# Power_USB.net
KiCad netlist of a schematic drawn in Altium Designer
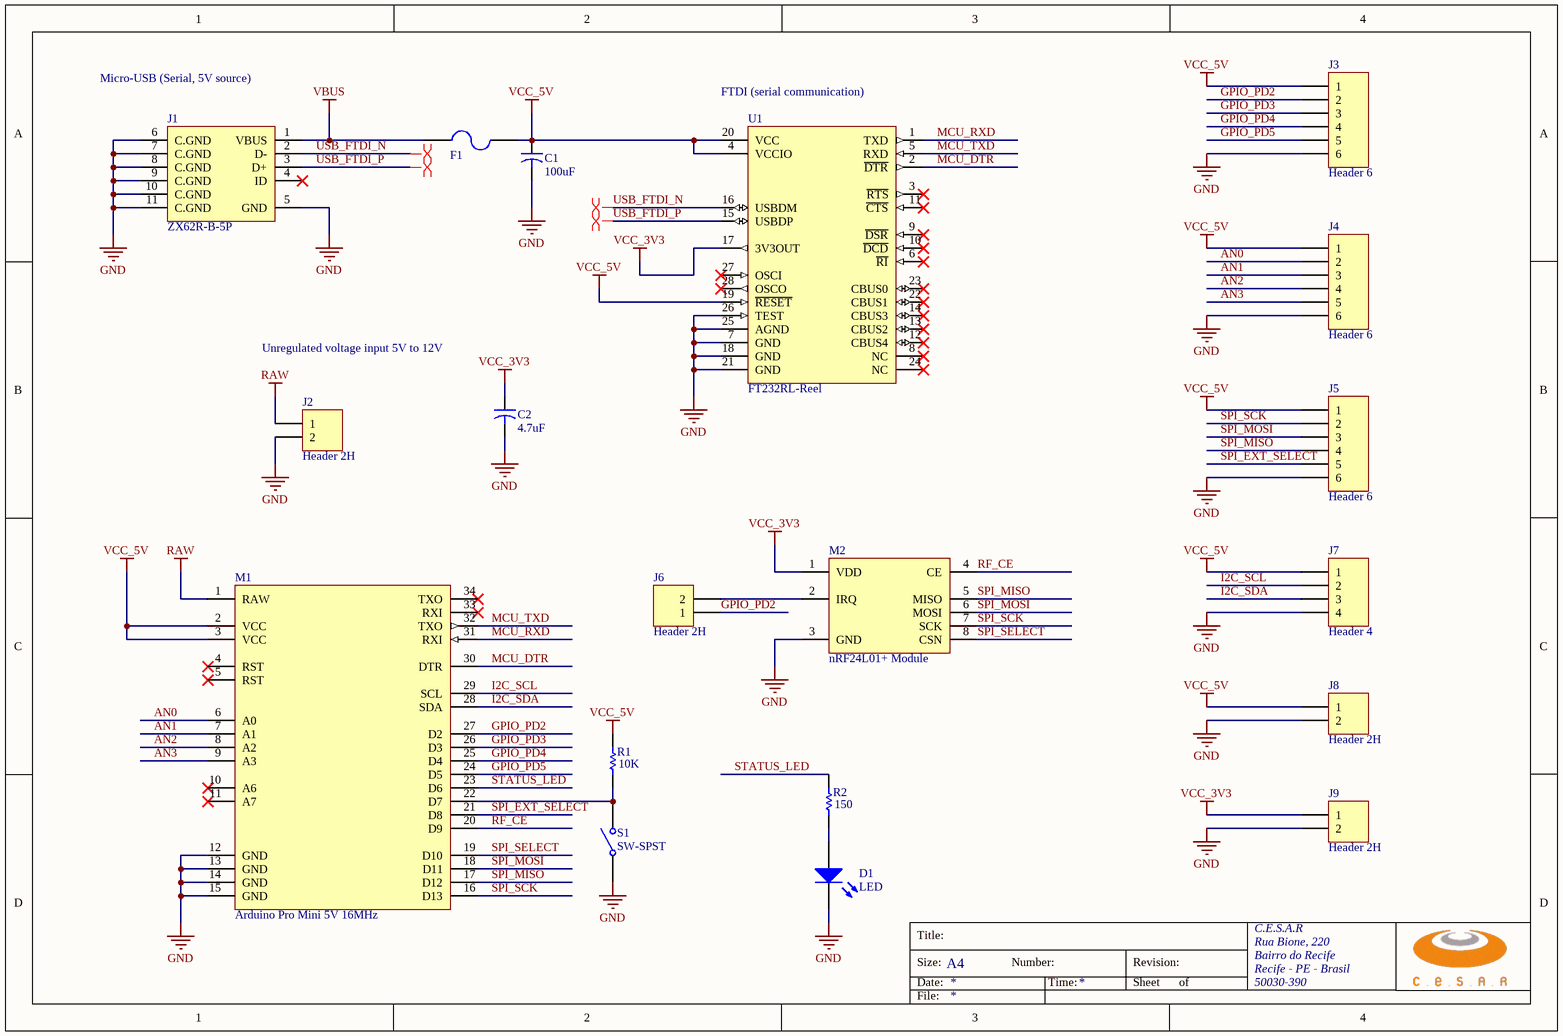
[diagram p0: Power_USB.SchDoc]

(export (version "E")
  (design (tool "Eeschema 10.0.6"))
  (components
    (comp (ref "C1")
      (value "100uF")
      (footprint "CAP Radial 100uF")
      (description "4.7µF 10V Ceramic Capacitor X5R 0603")
      (fields (field (name "Comment") "CAPC1608L") (field (name "PUBLISHER") "Altium Limited"))
      (libsource (lib "KNoT_Thing") (part "CAPC1608L"))
    )
    (comp (ref "C2")
      (value "4.7uF")
      (footprint "CAP RADIAL MINIATURE")
      (description "4.7µF 10V Ceramic Capacitor X5R 0603")
      (fields (field (name "Comment") "CAPC1608L") (field (name "PUBLISHER") "Altium Limited"))
      (libsource (lib "KNoT_Thing") (part "CAPC1608L"))
    )
    (comp (ref "D1")
      (value "LED")
      (footprint "LED")
      (description "Typical RED, GREEN, YELLOW, AMBER GaAs LED")
      (fields (field (name "PUBLISHER") "Altium Limited"))
      (libsource (lib "KNoT_Thing") (part "LED"))
    )
    (comp (ref "F1")
      (value "0402L050SLKR")
      (footprint "0805L")
      (description "PTC Resettable Fuse 6V 500mA Ih Surface Mount 0402 (1005 Metric), Concave")
      (libsource (lib "KNoT_Thing") (part "Fuse 2"))
    )
    (comp (ref "J1")
      (value "ZX62R-B-5P")
      (footprint "Micro USB b")
      (description "USB Connector")
      (libsource (lib "KNoT_Thing") (part "ZX62R-B-5P"))
    )
    (comp (ref "J2")
      (value "Header 2H")
      (footprint "HDR1X2")
      (description "Header, 2-Pin, Right Angle")
      (fields (field (name "PUBLISHER") "Altium Limited"))
      (libsource (lib "KNoT_Thing") (part "Header 2H"))
    )
    (comp (ref "J3")
      (value "Header 6")
      (footprint "HDR1X6")
      (description "Header, 6-Pin")
      (fields (field (name "PUBLISHER") "Altium Limited"))
      (libsource (lib "KNoT_Thing") (part "Header 6"))
    )
    (comp (ref "J4")
      (value "Header 6")
      (footprint "HDR1X6")
      (description "Header, 6-Pin")
      (fields (field (name "PUBLISHER") "Altium Limited"))
      (libsource (lib "KNoT_Thing") (part "Header 6"))
    )
    (comp (ref "J5")
      (value "Header 6")
      (footprint "HDR1X6")
      (description "Header, 6-Pin")
      (fields (field (name "PUBLISHER") "Altium Limited"))
      (libsource (lib "KNoT_Thing") (part "Header 6"))
    )
    (comp (ref "J6")
      (value "Header 2H")
      (footprint "HDR1X2")
      (description "Header, 2-Pin, Right Angle")
      (fields (field (name "PUBLISHER") "Altium Limited"))
      (libsource (lib "") (part "Header 2H_1"))
    )
    (comp (ref "J7")
      (value "Header 4")
      (footprint "HDR1X4")
      (description "Header, 4-Pin")
      (fields (field (name "PUBLISHER") "Altium Limited"))
      (libsource (lib "KNoT_Thing") (part "Header 4"))
    )
    (comp (ref "J8")
      (value "Header 2H")
      (footprint "HDR1X2")
      (description "Header, 2-Pin, Right Angle")
      (fields (field (name "PUBLISHER") "Altium Limited"))
      (libsource (lib "KNoT_Thing") (part "Header 2H"))
    )
    (comp (ref "J9")
      (value "Header 2H")
      (footprint "HDR1X2")
      (description "Header, 2-Pin, Right Angle")
      (fields (field (name "PUBLISHER") "Altium Limited"))
      (libsource (lib "KNoT_Thing") (part "Header 2H"))
    )
    (comp (ref "M1")
      (value "Arduino Pro Mini 5V 16MHz")
      (footprint "Arduino Pro Mini")
      (libsource (lib "KNoT_Thing") (part "Arduino Pro Mini 5V 16MHz"))
    )
    (comp (ref "M2")
      (value "nRF24L01+ Module")
      (footprint "nRF24L01+ Module")
      (libsource (lib "KNoT_Thing") (part "nRF24L01+ Module"))
    )
    (comp (ref "R1")
      (value "10K")
      (footprint "AXIAL-3mm")
      (description "Resistor")
      (fields (field (name "Comment") "Res1") (field (name "PUBLISHER") "Altium Limited"))
      (libsource (lib "KNoT_Thing") (part "Res1"))
    )
    (comp (ref "R2")
      (value "150")
      (footprint "AXIAL-3mm")
      (description "Resistor")
      (fields (field (name "Comment") "Res1") (field (name "PUBLISHER") "Altium Limited"))
      (libsource (lib "KNoT_Thing") (part "Res1"))
    )
    (comp (ref "S1")
      (value "SW-SPST")
      (footprint "SWITCH TS-1181")
      (description "Single-Pole, Single-Throw Switch")
      (fields (field (name "PUBLISHER") "Altium Limited"))
      (libsource (lib "KNoT_Thing") (part "SW-SPST"))
    )
    (comp (ref "U1")
      (value "FT232RL-Reel")
      (footprint "SSOP-28_N")
      (description "USB UART Asynchronous Serial Data Transfer Chip, 28-pin SSOP, Tape and Reel")
      (fields (field (name "MANUFACTURER") "FTDI"))
      (libsource (lib "KNoT_Thing") (part "FT232RL-Reel"))
    )
  )
  (nets
    (net (code "1") (name "/AN0") (class "Default")
      (node (ref "J4") (pin "2") (pinfunction "2_2") (pintype "passive"))
      (node (ref "M1") (pin "6") (pinfunction "A0_6") (pintype "passive"))
    )
    (net (code "2") (name "/AN1") (class "Default")
      (node (ref "J4") (pin "3") (pinfunction "3_3") (pintype "passive"))
      (node (ref "M1") (pin "7") (pinfunction "A1_7") (pintype "passive"))
    )
    (net (code "3") (name "/AN2") (class "Default")
      (node (ref "J4") (pin "4") (pinfunction "4_4") (pintype "passive"))
      (node (ref "M1") (pin "8") (pinfunction "A2_8") (pintype "passive"))
    )
    (net (code "4") (name "/AN3") (class "Default")
      (node (ref "J4") (pin "5") (pinfunction "5_5") (pintype "passive"))
      (node (ref "M1") (pin "9") (pinfunction "A3_9") (pintype "passive"))
    )
    (net (code "5") (name "/GPIO_PD2") (class "Default")
      (node (ref "J3") (pin "2") (pinfunction "2_2") (pintype "passive"))
      (node (ref "J6") (pin "1") (pinfunction "1_1") (pintype "passive"))
      (node (ref "M1") (pin "27") (pinfunction "D2_27") (pintype "passive"))
    )
    (net (code "6") (name "/GPIO_PD3") (class "Default")
      (node (ref "J3") (pin "3") (pinfunction "3_3") (pintype "passive"))
      (node (ref "M1") (pin "26") (pinfunction "D3_26") (pintype "passive"))
    )
    (net (code "7") (name "/GPIO_PD4") (class "Default")
      (node (ref "J3") (pin "4") (pinfunction "4_4") (pintype "passive"))
      (node (ref "M1") (pin "25") (pinfunction "D4_25") (pintype "passive"))
    )
    (net (code "8") (name "/GPIO_PD5") (class "Default")
      (node (ref "J3") (pin "5") (pinfunction "5_5") (pintype "passive"))
      (node (ref "M1") (pin "24") (pinfunction "D5_24") (pintype "passive"))
    )
    (net (code "9") (name "/I2C_SCL") (class "Default")
      (node (ref "J7") (pin "2") (pinfunction "2_2") (pintype "passive"))
      (node (ref "M1") (pin "29") (pinfunction "SCL_29") (pintype "passive"))
    )
    (net (code "10") (name "/I2C_SDA") (class "Default")
      (node (ref "J7") (pin "3") (pinfunction "3_3") (pintype "passive"))
      (node (ref "M1") (pin "28") (pinfunction "SDA_28") (pintype "passive"))
    )
    (net (code "11") (name "/MCU_DTR") (class "Default")
      (node (ref "M1") (pin "30") (pinfunction "DTR_30") (pintype "passive"))
      (node (ref "U1") (pin "2") (pinfunction "~{DTR}_2") (pintype "output"))
    )
    (net (code "12") (name "/MCU_RXD") (class "Default")
      (node (ref "M1") (pin "31") (pinfunction "RXI_31") (pintype "input"))
      (node (ref "U1") (pin "1") (pinfunction "TXD_1") (pintype "output"))
    )
    (net (code "13") (name "/MCU_TXD") (class "Default")
      (node (ref "M1") (pin "32") (pinfunction "TXO_32") (pintype "output"))
      (node (ref "U1") (pin "5") (pinfunction "RXD_5") (pintype "input"))
    )
    (net (code "14") (name "/RF_CE") (class "Default")
      (node (ref "M1") (pin "20") (pinfunction "D9_20") (pintype "passive"))
      (node (ref "M2") (pin "4") (pinfunction "CE_4") (pintype "passive"))
    )
    (net (code "15") (name "/SPI_EXT_SELECT") (class "Default")
      (node (ref "J5") (pin "5") (pinfunction "5_5") (pintype "passive"))
      (node (ref "M1") (pin "21") (pinfunction "D8_21") (pintype "passive"))
    )
    (net (code "16") (name "/SPI_MISO") (class "Default")
      (node (ref "J5") (pin "4") (pinfunction "4_4") (pintype "passive"))
      (node (ref "M1") (pin "17") (pinfunction "D12_17") (pintype "passive"))
      (node (ref "M2") (pin "5") (pinfunction "MISO_5") (pintype "passive"))
    )
    (net (code "17") (name "/SPI_MOSI") (class "Default")
      (node (ref "J5") (pin "3") (pinfunction "3_3") (pintype "passive"))
      (node (ref "M1") (pin "18") (pinfunction "D11_18") (pintype "passive"))
      (node (ref "M2") (pin "6") (pinfunction "MOSI_6") (pintype "passive"))
    )
    (net (code "18") (name "/SPI_SCK") (class "Default")
      (node (ref "J5") (pin "2") (pinfunction "2_2") (pintype "passive"))
      (node (ref "M1") (pin "16") (pinfunction "D13_16") (pintype "passive"))
      (node (ref "M2") (pin "7") (pinfunction "SCK_7") (pintype "passive"))
    )
    (net (code "19") (name "/SPI_SELECT") (class "Default")
      (node (ref "M1") (pin "19") (pinfunction "D10_19") (pintype "passive"))
      (node (ref "M2") (pin "8") (pinfunction "CSN_8") (pintype "passive"))
    )
    (net (code "20") (name "/STATUS_LED") (class "Default")
      (node (ref "M1") (pin "23") (pinfunction "D6_23") (pintype "passive"))
      (node (ref "R2") (pin "1") (pinfunction "1_1") (pintype "passive"))
    )
    (net (code "21") (name "/USB_FTDI_N") (class "Default")
      (node (ref "J1") (pin "2") (pinfunction "D-_2") (pintype "passive"))
      (node (ref "U1") (pin "16") (pinfunction "USBDM_16") (pintype "bidirectional"))
    )
    (net (code "22") (name "/USB_FTDI_P") (class "Default")
      (node (ref "J1") (pin "3") (pinfunction "D+_3") (pintype "passive"))
      (node (ref "U1") (pin "15") (pinfunction "USBDP_15") (pintype "bidirectional"))
    )
    (net (code "23") (name "GND") (class "Default")
      (node (ref "C1") (pin "2") (pinfunction "2_2") (pintype "passive"))
      (node (ref "C2") (pin "2") (pinfunction "2_2") (pintype "passive"))
      (node (ref "D1") (pin "2") (pinfunction "K_2") (pintype "passive"))
      (node (ref "J1") (pin "10") (pinfunction "C.GND_10") (pintype "passive"))
      (node (ref "J1") (pin "11") (pinfunction "C.GND_11") (pintype "passive"))
      (node (ref "J1") (pin "5") (pinfunction "GND_5") (pintype "passive"))
      (node (ref "J1") (pin "6") (pinfunction "C.GND_6") (pintype "passive"))
      (node (ref "J1") (pin "7") (pinfunction "C.GND_7") (pintype "passive"))
      (node (ref "J1") (pin "8") (pinfunction "C.GND_8") (pintype "passive"))
      (node (ref "J1") (pin "9") (pinfunction "C.GND_9") (pintype "passive"))
      (node (ref "J2") (pin "2") (pinfunction "2_2") (pintype "passive"))
      (node (ref "J3") (pin "6") (pinfunction "6_6") (pintype "passive"))
      (node (ref "J4") (pin "6") (pinfunction "6_6") (pintype "passive"))
      (node (ref "J5") (pin "6") (pinfunction "6_6") (pintype "passive"))
      (node (ref "J7") (pin "4") (pinfunction "4_4") (pintype "passive"))
      (node (ref "J8") (pin "2") (pinfunction "2_2") (pintype "passive"))
      (node (ref "J9") (pin "2") (pinfunction "2_2") (pintype "passive"))
      (node (ref "M1") (pin "12") (pinfunction "GND_12") (pintype "passive"))
      (node (ref "M1") (pin "13") (pinfunction "GND_13") (pintype "passive"))
      (node (ref "M1") (pin "14") (pinfunction "GND_14") (pintype "passive"))
      (node (ref "M1") (pin "15") (pinfunction "GND_15") (pintype "passive"))
      (node (ref "M2") (pin "3") (pinfunction "GND_3") (pintype "passive"))
      (node (ref "S1") (pin "1") (pinfunction "COMMON_1") (pintype "passive"))
      (node (ref "U1") (pin "18") (pinfunction "GND_18") (pintype "power_in"))
      (node (ref "U1") (pin "21") (pinfunction "GND_21") (pintype "power_in"))
      (node (ref "U1") (pin "25") (pinfunction "AGND_25") (pintype "power_in"))
      (node (ref "U1") (pin "26") (pinfunction "TEST_26") (pintype "input"))
      (node (ref "U1") (pin "7") (pinfunction "GND_7") (pintype "power_in"))
    )
    (net (code "24") (name "Net-(D1-A)") (class "Default")
      (node (ref "D1") (pin "1") (pinfunction "A_1") (pintype "passive"))
      (node (ref "R2") (pin "2") (pinfunction "2_2") (pintype "passive"))
    )
    (net (code "25") (name "Net-(M1-D7)") (class "Default")
      (node (ref "M1") (pin "22") (pinfunction "D7_22") (pintype "passive"))
      (node (ref "R1") (pin "2") (pinfunction "2_2") (pintype "passive"))
      (node (ref "S1") (pin "2") (pinfunction "NO_2") (pintype "passive"))
    )
    (net (code "26") (name "Net-(M2-IRQ)") (class "Default")
      (node (ref "J6") (pin "2") (pinfunction "2_2") (pintype "passive"))
      (node (ref "M2") (pin "2") (pinfunction "IRQ_2") (pintype "passive"))
    )
    (net (code "27") (name "RAW") (class "Default")
      (node (ref "J2") (pin "1") (pinfunction "1_1") (pintype "passive"))
      (node (ref "M1") (pin "1") (pinfunction "RAW_1") (pintype "passive"))
    )
    (net (code "28") (name "VBUS") (class "Default")
      (node (ref "F1") (pin "1") (pinfunction "1_1") (pintype "passive"))
      (node (ref "J1") (pin "1") (pinfunction "VBUS_1") (pintype "passive"))
    )
    (net (code "29") (name "VCC_3V3") (class "Default")
      (node (ref "C2") (pin "1") (pinfunction "1_1") (pintype "passive"))
      (node (ref "J9") (pin "1") (pinfunction "1_1") (pintype "passive"))
      (node (ref "M2") (pin "1") (pinfunction "VDD_1") (pintype "passive"))
      (node (ref "U1") (pin "17") (pinfunction "3V3OUT_17") (pintype "output"))
    )
    (net (code "30") (name "VCC_5V") (class "Default")
      (node (ref "C1") (pin "1") (pinfunction "1_1") (pintype "passive"))
      (node (ref "F1") (pin "2") (pinfunction "2_2") (pintype "passive"))
      (node (ref "J3") (pin "1") (pinfunction "1_1") (pintype "passive"))
      (node (ref "J4") (pin "1") (pinfunction "1_1") (pintype "passive"))
      (node (ref "J5") (pin "1") (pinfunction "1_1") (pintype "passive"))
      (node (ref "J7") (pin "1") (pinfunction "1_1") (pintype "passive"))
      (node (ref "J8") (pin "1") (pinfunction "1_1") (pintype "passive"))
      (node (ref "M1") (pin "2") (pinfunction "VCC_2") (pintype "passive"))
      (node (ref "M1") (pin "3") (pinfunction "VCC_3") (pintype "passive"))
      (node (ref "R1") (pin "1") (pinfunction "1_1") (pintype "passive"))
      (node (ref "U1") (pin "19") (pinfunction "~{RESET}_19") (pintype "input"))
      (node (ref "U1") (pin "20") (pinfunction "VCC_20") (pintype "power_in"))
      (node (ref "U1") (pin "4") (pinfunction "VCCIO_4") (pintype "power_in"))
    )
    (net (code "31") (name "unconnected-(J1-ID-Pad4)") (class "Default")
      (node (ref "J1") (pin "4") (pinfunction "ID_4") (pintype "passive+no_connect"))
    )
    (net (code "32") (name "unconnected-(M1-A6-Pad10)") (class "Default")
      (node (ref "M1") (pin "10") (pinfunction "A6_10") (pintype "passive+no_connect"))
    )
    (net (code "33") (name "unconnected-(M1-A7-Pad11)") (class "Default")
      (node (ref "M1") (pin "11") (pinfunction "A7_11") (pintype "passive+no_connect"))
    )
    (net (code "34") (name "unconnected-(M1-RST-Pad4)") (class "Default")
      (node (ref "M1") (pin "4") (pinfunction "RST_4") (pintype "passive+no_connect"))
    )
    (net (code "35") (name "unconnected-(M1-RST-Pad5)") (class "Default")
      (node (ref "M1") (pin "5") (pinfunction "RST_5") (pintype "passive+no_connect"))
    )
    (net (code "36") (name "unconnected-(M1-RXI-Pad33)") (class "Default")
      (node (ref "M1") (pin "33") (pinfunction "RXI_33") (pintype "passive+no_connect"))
    )
    (net (code "37") (name "unconnected-(M1-TXO-Pad34)") (class "Default")
      (node (ref "M1") (pin "34") (pinfunction "TXO_34") (pintype "passive+no_connect"))
    )
    (net (code "38") (name "unconnected-(U1-CBUS0-Pad23)") (class "Default")
      (node (ref "U1") (pin "23") (pinfunction "CBUS0_23") (pintype "bidirectional+no_connect"))
    )
    (net (code "39") (name "unconnected-(U1-CBUS1-Pad22)") (class "Default")
      (node (ref "U1") (pin "22") (pinfunction "CBUS1_22") (pintype "bidirectional+no_connect"))
    )
    (net (code "40") (name "unconnected-(U1-CBUS2-Pad13)") (class "Default")
      (node (ref "U1") (pin "13") (pinfunction "CBUS2_13") (pintype "bidirectional+no_connect"))
    )
    (net (code "41") (name "unconnected-(U1-CBUS3-Pad14)") (class "Default")
      (node (ref "U1") (pin "14") (pinfunction "CBUS3_14") (pintype "bidirectional+no_connect"))
    )
    (net (code "42") (name "unconnected-(U1-CBUS4-Pad12)") (class "Default")
      (node (ref "U1") (pin "12") (pinfunction "CBUS4_12") (pintype "bidirectional+no_connect"))
    )
    (net (code "43") (name "unconnected-(U1-NC-Pad8)") (class "Default")
      (node (ref "U1") (pin "8") (pinfunction "NC_8") (pintype "passive+no_connect"))
    )
    (net (code "44") (name "unconnected-(U1-NC-Pad24)") (class "Default")
      (node (ref "U1") (pin "24") (pinfunction "NC_24") (pintype "passive+no_connect"))
    )
    (net (code "45") (name "unconnected-(U1-OSCI-Pad27)") (class "Default")
      (node (ref "U1") (pin "27") (pinfunction "OSCI_27") (pintype "input+no_connect"))
    )
    (net (code "46") (name "unconnected-(U1-OSCO-Pad28)") (class "Default")
      (node (ref "U1") (pin "28") (pinfunction "OSCO_28") (pintype "output+no_connect"))
    )
    (net (code "47") (name "unconnected-(U1-~{CTS}-Pad11)") (class "Default")
      (node (ref "U1") (pin "11") (pinfunction "~{CTS}_11") (pintype "input+no_connect"))
    )
    (net (code "48") (name "unconnected-(U1-~{DCD}-Pad10)") (class "Default")
      (node (ref "U1") (pin "10") (pinfunction "~{DCD}_10") (pintype "input+no_connect"))
    )
    (net (code "49") (name "unconnected-(U1-~{DSR}-Pad9)") (class "Default")
      (node (ref "U1") (pin "9") (pinfunction "~{DSR}_9") (pintype "input+no_connect"))
    )
    (net (code "50") (name "unconnected-(U1-~{RI}-Pad6)") (class "Default")
      (node (ref "U1") (pin "6") (pinfunction "~{RI}_6") (pintype "input+no_connect"))
    )
    (net (code "51") (name "unconnected-(U1-~{RTS}-Pad3)") (class "Default")
      (node (ref "U1") (pin "3") (pinfunction "~{RTS}_3") (pintype "output+no_connect"))
    )
  )
)
